# Input_Conditioning.net
KiCad netlist of a schematic drawn in Altium Designer
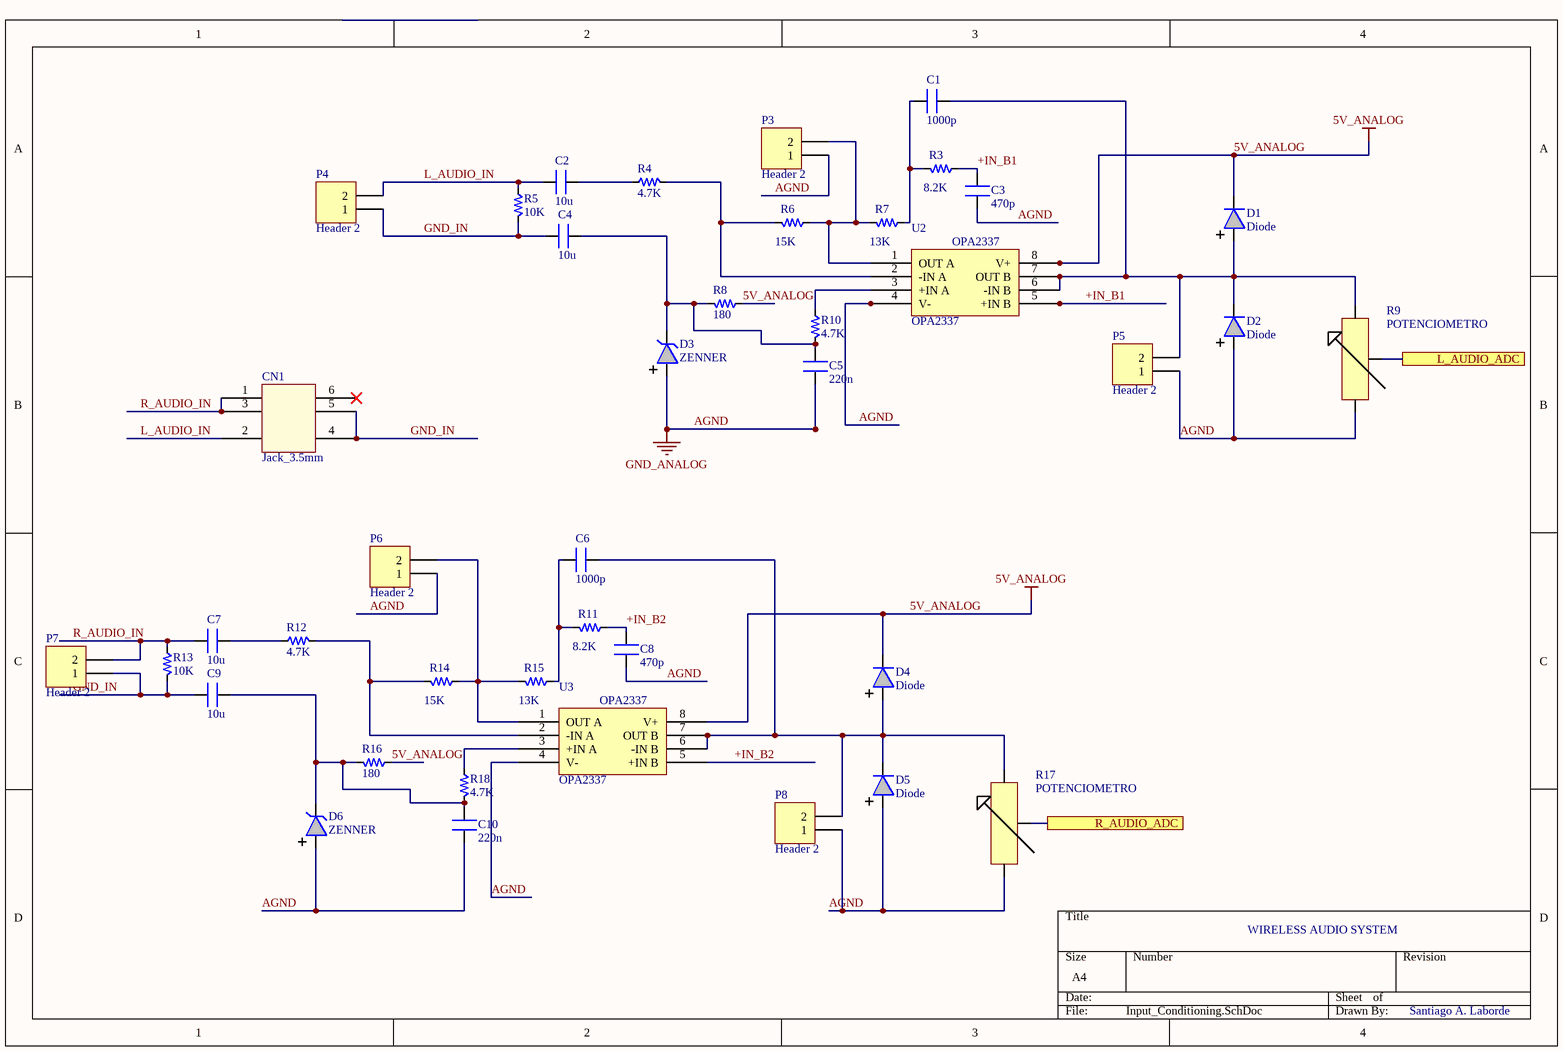
[diagram p0: Input_Conditioning.SchDoc]

(export (version "E")
  (design (tool "Eeschema 10.0.6"))
  (components
    (comp (ref "C1")
      (value "1000p")
      (footprint "C_0805")
      (description "Non Polarised Capacitor")
      (libsource (lib "TD2_Project") (part "Capacitor_NP"))
    )
    (comp (ref "C2")
      (value "10u")
      (footprint "RAD-0.1")
      (description "Non Polarised Capacitor")
      (libsource (lib "TD2_Project") (part "Capacitor_NP"))
    )
    (comp (ref "C3")
      (value "470p")
      (footprint "C_0805")
      (description "Non Polarised Capacitor")
      (libsource (lib "TD2_Project") (part "Capacitor_NP"))
    )
    (comp (ref "C4")
      (value "10u")
      (footprint "RAD-0.1")
      (description "Non Polarised Capacitor")
      (libsource (lib "TD2_Project") (part "Capacitor_NP"))
    )
    (comp (ref "C5")
      (value "220n")
      (footprint "C_0805")
      (description "Non Polarised Capacitor")
      (libsource (lib "TD2_Project") (part "Capacitor_NP"))
    )
    (comp (ref "C6")
      (value "1000p")
      (footprint "C_0805")
      (description "Non Polarised Capacitor")
      (libsource (lib "TD2_Project") (part "Capacitor_NP"))
    )
    (comp (ref "C7")
      (value "10u")
      (footprint "RAD-0.1")
      (description "Non Polarised Capacitor")
      (libsource (lib "TD2_Project") (part "Capacitor_NP"))
    )
    (comp (ref "C8")
      (value "470p")
      (footprint "C_0805")
      (description "Non Polarised Capacitor")
      (libsource (lib "TD2_Project") (part "Capacitor_NP"))
    )
    (comp (ref "C9")
      (value "10u")
      (footprint "RAD-0.1")
      (description "Non Polarised Capacitor")
      (libsource (lib "TD2_Project") (part "Capacitor_NP"))
    )
    (comp (ref "C10")
      (value "220n")
      (footprint "C_0805")
      (description "Non Polarised Capacitor")
      (libsource (lib "TD2_Project") (part "Capacitor_NP"))
    )
    (comp (ref "CN1")
      (value "Jack_3.5mm")
      (footprint "JACK_3.5mm")
      (libsource (lib "TD2_Project") (part "Jack_3.5mm"))
    )
    (comp (ref "D1") (value "Diode") (footprint "LED_0805") (libsource (lib "TD2_Project") (part "Diode")))
    (comp (ref "D2") (value "Diode") (footprint "LED_0805") (libsource (lib "TD2_Project") (part "Diode")))
    (comp (ref "D3") (value "ZENNER") (footprint "SOD123") (libsource (lib "TD2_Project") (part "ZENNER")))
    (comp (ref "D4") (value "Diode") (footprint "LED_0805") (libsource (lib "TD2_Project") (part "Diode")))
    (comp (ref "D5") (value "Diode") (footprint "LED_0805") (libsource (lib "TD2_Project") (part "Diode")))
    (comp (ref "D6") (value "ZENNER") (footprint "SOD123") (libsource (lib "TD2_Project") (part "ZENNER")))
    (comp (ref "P3")
      (value "Header 2")
      (footprint "Header1x2")
      (description "Header, 2-Pin")
      (fields (field (name "PUBLISHER") "Altium Limited"))
      (libsource (lib "Miscellaneous Connectors") (part "Header 2"))
    )
    (comp (ref "P4")
      (value "Header 2")
      (footprint "Header1x2")
      (description "Header, 2-Pin")
      (fields (field (name "PUBLISHER") "Altium Limited"))
      (libsource (lib "Miscellaneous Connectors") (part "Header 2"))
    )
    (comp (ref "P5")
      (value "Header 2")
      (footprint "Header1x2")
      (description "Header, 2-Pin")
      (fields (field (name "PUBLISHER") "Altium Limited"))
      (libsource (lib "Miscellaneous Connectors") (part "Header 2"))
    )
    (comp (ref "P6")
      (value "Header 2")
      (footprint "Header1x2")
      (description "Header, 2-Pin")
      (fields (field (name "PUBLISHER") "Altium Limited"))
      (libsource (lib "Miscellaneous Connectors") (part "Header 2"))
    )
    (comp (ref "P7")
      (value "Header 2")
      (footprint "Header1x2")
      (description "Header, 2-Pin")
      (fields (field (name "PUBLISHER") "Altium Limited"))
      (libsource (lib "Miscellaneous Connectors") (part "Header 2"))
    )
    (comp (ref "P8")
      (value "Header 2")
      (footprint "Header1x2")
      (description "Header, 2-Pin")
      (fields (field (name "PUBLISHER") "Altium Limited"))
      (libsource (lib "Miscellaneous Connectors") (part "Header 2"))
    )
    (comp (ref "R3") (value "8.2K") (footprint "R_0805") (libsource (lib "TD2_Project") (part "Resistor")))
    (comp (ref "R4") (value "4.7K") (footprint "R_0805") (libsource (lib "TD2_Project") (part "Resistor")))
    (comp (ref "R5") (value "10K") (footprint "R_0805") (libsource (lib "TD2_Project") (part "Resistor")))
    (comp (ref "R6") (value "15K") (footprint "R_0805") (libsource (lib "TD2_Project") (part "Resistor")))
    (comp (ref "R7") (value "13K") (footprint "R_0805") (libsource (lib "TD2_Project") (part "Resistor")))
    (comp (ref "R8") (value "180") (footprint "R_0805") (libsource (lib "TD2_Project") (part "Resistor")))
    (comp (ref "R9")
      (value "POTENCIOMETRO")
      (footprint "Potenciometro")
      (libsource (lib "TD2_Project") (part "POTENCIOMETRO"))
    )
    (comp (ref "R10") (value "4.7K") (footprint "R_0805") (libsource (lib "TD2_Project") (part "Resistor")))
    (comp (ref "R11") (value "8.2K") (footprint "R_0805") (libsource (lib "TD2_Project") (part "Resistor")))
    (comp (ref "R12") (value "4.7K") (footprint "R_0805") (libsource (lib "TD2_Project") (part "Resistor")))
    (comp (ref "R13") (value "10K") (footprint "R_0805") (libsource (lib "TD2_Project") (part "Resistor")))
    (comp (ref "R14") (value "15K") (footprint "R_0805") (libsource (lib "TD2_Project") (part "Resistor")))
    (comp (ref "R15") (value "13K") (footprint "R_0805") (libsource (lib "TD2_Project") (part "Resistor")))
    (comp (ref "R16") (value "180") (footprint "R_0805") (libsource (lib "TD2_Project") (part "Resistor")))
    (comp (ref "R17")
      (value "POTENCIOMETRO")
      (footprint "Potenciometro")
      (libsource (lib "TD2_Project") (part "POTENCIOMETRO"))
    )
    (comp (ref "R18") (value "4.7K") (footprint "R_0805") (libsource (lib "TD2_Project") (part "Resistor")))
    (comp (ref "U2") (value "OPA2337") (footprint "SOIC-8N") (libsource (lib "TD2_Project") (part "OPA2337")))
    (comp (ref "U3") (value "OPA2337") (footprint "SOIC-8N") (libsource (lib "TD2_Project") (part "OPA2337")))
  )
  (nets
    (net (code "1") (name "/+IN_B1") (class "Default")
      (node (ref "C3") (pin "1") (pinfunction "1_1") (pintype "passive"))
      (node (ref "R3") (pin "2") (pinfunction "2_2") (pintype "passive"))
      (node (ref "U2") (pin "5") (pinfunction "+IN_B_5") (pintype "passive"))
    )
    (net (code "2") (name "/+IN_B2") (class "Default")
      (node (ref "C8") (pin "1") (pinfunction "1_1") (pintype "passive"))
      (node (ref "R11") (pin "2") (pinfunction "2_2") (pintype "passive"))
      (node (ref "U3") (pin "5") (pinfunction "+IN_B_5") (pintype "passive"))
    )
    (net (code "3") (name "/GND_IN") (class "Default")
      (node (ref "C4") (pin "1") (pinfunction "1_1") (pintype "passive"))
      (node (ref "C9") (pin "1") (pinfunction "1_1") (pintype "passive"))
      (node (ref "CN1") (pin "4") (pintype "passive"))
      (node (ref "CN1") (pin "5") (pintype "passive"))
      (node (ref "P4") (pin "1") (pinfunction "1_1") (pintype "passive"))
      (node (ref "P7") (pin "1") (pinfunction "1_1") (pintype "passive"))
      (node (ref "R13") (pin "1") (pinfunction "1_1") (pintype "passive"))
      (node (ref "R5") (pin "1") (pinfunction "1_1") (pintype "passive"))
    )
    (net (code "4") (name "/L_AUDIO_ADC") (class "Default")
      (node (ref "R9") (pin "3") (pinfunction "3_3") (pintype "passive"))
    )
    (net (code "5") (name "/L_AUDIO_IN") (class "Default")
      (node (ref "C2") (pin "2") (pinfunction "2_2") (pintype "passive"))
      (node (ref "CN1") (pin "2") (pintype "passive"))
      (node (ref "P4") (pin "2") (pinfunction "2_2") (pintype "passive"))
      (node (ref "R5") (pin "2") (pinfunction "2_2") (pintype "passive"))
    )
    (net (code "6") (name "/R_AUDIO_ADC") (class "Default")
      (node (ref "R17") (pin "3") (pinfunction "3_3") (pintype "passive"))
    )
    (net (code "7") (name "/R_AUDIO_IN") (class "Default")
      (node (ref "C7") (pin "2") (pinfunction "2_2") (pintype "passive"))
      (node (ref "CN1") (pin "1") (pintype "passive"))
      (node (ref "CN1") (pin "3") (pintype "passive"))
      (node (ref "P7") (pin "2") (pinfunction "2_2") (pintype "passive"))
      (node (ref "R13") (pin "2") (pinfunction "2_2") (pintype "passive"))
    )
    (net (code "8") (name "5V_ANALOG") (class "Default")
      (node (ref "D1") (pin "2") (pinfunction "16_2") (pintype "passive"))
      (node (ref "D4") (pin "2") (pinfunction "16_2") (pintype "passive"))
      (node (ref "R16") (pin "2") (pinfunction "2_2") (pintype "passive"))
      (node (ref "R8") (pin "2") (pinfunction "2_2") (pintype "passive"))
      (node (ref "U2") (pin "8") (pinfunction "V+_8") (pintype "passive"))
      (node (ref "U3") (pin "8") (pinfunction "V+_8") (pintype "passive"))
    )
    (net (code "9") (name "GND_ANALOG") (class "Default")
      (node (ref "C10") (pin "2") (pinfunction "2_2") (pintype "passive"))
      (node (ref "C3") (pin "2") (pinfunction "2_2") (pintype "passive"))
      (node (ref "C5") (pin "2") (pinfunction "2_2") (pintype "passive"))
      (node (ref "C8") (pin "2") (pinfunction "2_2") (pintype "passive"))
      (node (ref "D2") (pin "1") (pinfunction "15_1") (pintype "passive"))
      (node (ref "D3") (pin "1") (pinfunction "15_1") (pintype "passive"))
      (node (ref "D5") (pin "1") (pinfunction "15_1") (pintype "passive"))
      (node (ref "D6") (pin "1") (pinfunction "15_1") (pintype "passive"))
      (node (ref "P3") (pin "1") (pinfunction "1_1") (pintype "passive"))
      (node (ref "P5") (pin "1") (pinfunction "1_1") (pintype "passive"))
      (node (ref "P6") (pin "1") (pinfunction "1_1") (pintype "passive"))
      (node (ref "P8") (pin "1") (pinfunction "1_1") (pintype "passive"))
      (node (ref "R17") (pin "2") (pinfunction "2_2") (pintype "passive"))
      (node (ref "R9") (pin "2") (pinfunction "2_2") (pintype "passive"))
      (node (ref "U2") (pin "4") (pinfunction "V-_4") (pintype "passive"))
      (node (ref "U3") (pin "4") (pinfunction "V-_4") (pintype "passive"))
    )
    (net (code "10") (name "Net-(C1-Pad1)") (class "Default")
      (node (ref "C1") (pin "1") (pinfunction "1_1") (pintype "passive"))
      (node (ref "R3") (pin "1") (pinfunction "1_1") (pintype "passive"))
      (node (ref "R7") (pin "2") (pinfunction "2_2") (pintype "passive"))
    )
    (net (code "11") (name "Net-(C2-Pad1)") (class "Default")
      (node (ref "C2") (pin "1") (pinfunction "1_1") (pintype "passive"))
      (node (ref "R4") (pin "2") (pinfunction "2_2") (pintype "passive"))
    )
    (net (code "12") (name "Net-(C4-Pad2)") (class "Default")
      (node (ref "C4") (pin "2") (pinfunction "2_2") (pintype "passive"))
      (node (ref "C5") (pin "1") (pinfunction "1_1") (pintype "passive"))
      (node (ref "D3") (pin "2") (pintype "passive"))
      (node (ref "R10") (pin "1") (pinfunction "1_1") (pintype "passive"))
      (node (ref "R8") (pin "1") (pinfunction "1_1") (pintype "passive"))
    )
    (net (code "13") (name "Net-(C6-Pad1)") (class "Default")
      (node (ref "C6") (pin "1") (pinfunction "1_1") (pintype "passive"))
      (node (ref "R11") (pin "1") (pinfunction "1_1") (pintype "passive"))
      (node (ref "R15") (pin "2") (pinfunction "2_2") (pintype "passive"))
    )
    (net (code "14") (name "Net-(C7-Pad1)") (class "Default")
      (node (ref "C7") (pin "1") (pinfunction "1_1") (pintype "passive"))
      (node (ref "R12") (pin "2") (pinfunction "2_2") (pintype "passive"))
    )
    (net (code "15") (name "Net-(C10-Pad1)") (class "Default")
      (node (ref "C10") (pin "1") (pinfunction "1_1") (pintype "passive"))
      (node (ref "C9") (pin "2") (pinfunction "2_2") (pintype "passive"))
      (node (ref "D6") (pin "2") (pintype "passive"))
      (node (ref "R16") (pin "1") (pinfunction "1_1") (pintype "passive"))
      (node (ref "R18") (pin "1") (pinfunction "1_1") (pintype "passive"))
    )
    (net (code "16") (name "Net-(D1-15)") (class "Default")
      (node (ref "C1") (pin "2") (pinfunction "2_2") (pintype "passive"))
      (node (ref "D1") (pin "1") (pinfunction "15_1") (pintype "passive"))
      (node (ref "D2") (pin "2") (pinfunction "16_2") (pintype "passive"))
      (node (ref "P5") (pin "2") (pinfunction "2_2") (pintype "passive"))
      (node (ref "R9") (pin "1") (pinfunction "1_1") (pintype "passive"))
      (node (ref "U2") (pin "6") (pinfunction "-IN_B_6") (pintype "passive"))
      (node (ref "U2") (pin "7") (pinfunction "OUT_B_7") (pintype "passive"))
    )
    (net (code "17") (name "Net-(D4-15)") (class "Default")
      (node (ref "C6") (pin "2") (pinfunction "2_2") (pintype "passive"))
      (node (ref "D4") (pin "1") (pinfunction "15_1") (pintype "passive"))
      (node (ref "D5") (pin "2") (pinfunction "16_2") (pintype "passive"))
      (node (ref "P8") (pin "2") (pinfunction "2_2") (pintype "passive"))
      (node (ref "R17") (pin "1") (pinfunction "1_1") (pintype "passive"))
      (node (ref "U3") (pin "6") (pinfunction "-IN_B_6") (pintype "passive"))
      (node (ref "U3") (pin "7") (pinfunction "OUT_B_7") (pintype "passive"))
    )
    (net (code "18") (name "Net-(U2-+IN_A)") (class "Default")
      (node (ref "R10") (pin "2") (pinfunction "2_2") (pintype "passive"))
      (node (ref "U2") (pin "3") (pinfunction "+IN_A_3") (pintype "passive"))
    )
    (net (code "19") (name "Net-(U2--IN_A)") (class "Default")
      (node (ref "R4") (pin "1") (pinfunction "1_1") (pintype "passive"))
      (node (ref "R6") (pin "1") (pinfunction "1_1") (pintype "passive"))
      (node (ref "U2") (pin "2") (pinfunction "-IN_A_2") (pintype "passive"))
    )
    (net (code "20") (name "Net-(U2-OUT_A)") (class "Default")
      (node (ref "P3") (pin "2") (pinfunction "2_2") (pintype "passive"))
      (node (ref "R6") (pin "2") (pinfunction "2_2") (pintype "passive"))
      (node (ref "R7") (pin "1") (pinfunction "1_1") (pintype "passive"))
      (node (ref "U2") (pin "1") (pinfunction "OUT_A_1") (pintype "passive"))
    )
    (net (code "21") (name "Net-(U3-+IN_A)") (class "Default")
      (node (ref "R18") (pin "2") (pinfunction "2_2") (pintype "passive"))
      (node (ref "U3") (pin "3") (pinfunction "+IN_A_3") (pintype "passive"))
    )
    (net (code "22") (name "Net-(U3--IN_A)") (class "Default")
      (node (ref "R12") (pin "1") (pinfunction "1_1") (pintype "passive"))
      (node (ref "R14") (pin "1") (pinfunction "1_1") (pintype "passive"))
      (node (ref "U3") (pin "2") (pinfunction "-IN_A_2") (pintype "passive"))
    )
    (net (code "23") (name "Net-(U3-OUT_A)") (class "Default")
      (node (ref "P6") (pin "2") (pinfunction "2_2") (pintype "passive"))
      (node (ref "R14") (pin "2") (pinfunction "2_2") (pintype "passive"))
      (node (ref "R15") (pin "1") (pinfunction "1_1") (pintype "passive"))
      (node (ref "U3") (pin "1") (pinfunction "OUT_A_1") (pintype "passive"))
    )
    (net (code "24") (name "unconnected-(CN1-Pad6)") (class "Default")
      (node (ref "CN1") (pin "6") (pintype "passive+no_connect"))
    )
  )
)
